# Microcontrolador.net
KiCad netlist of a schematic drawn in Altium Designer
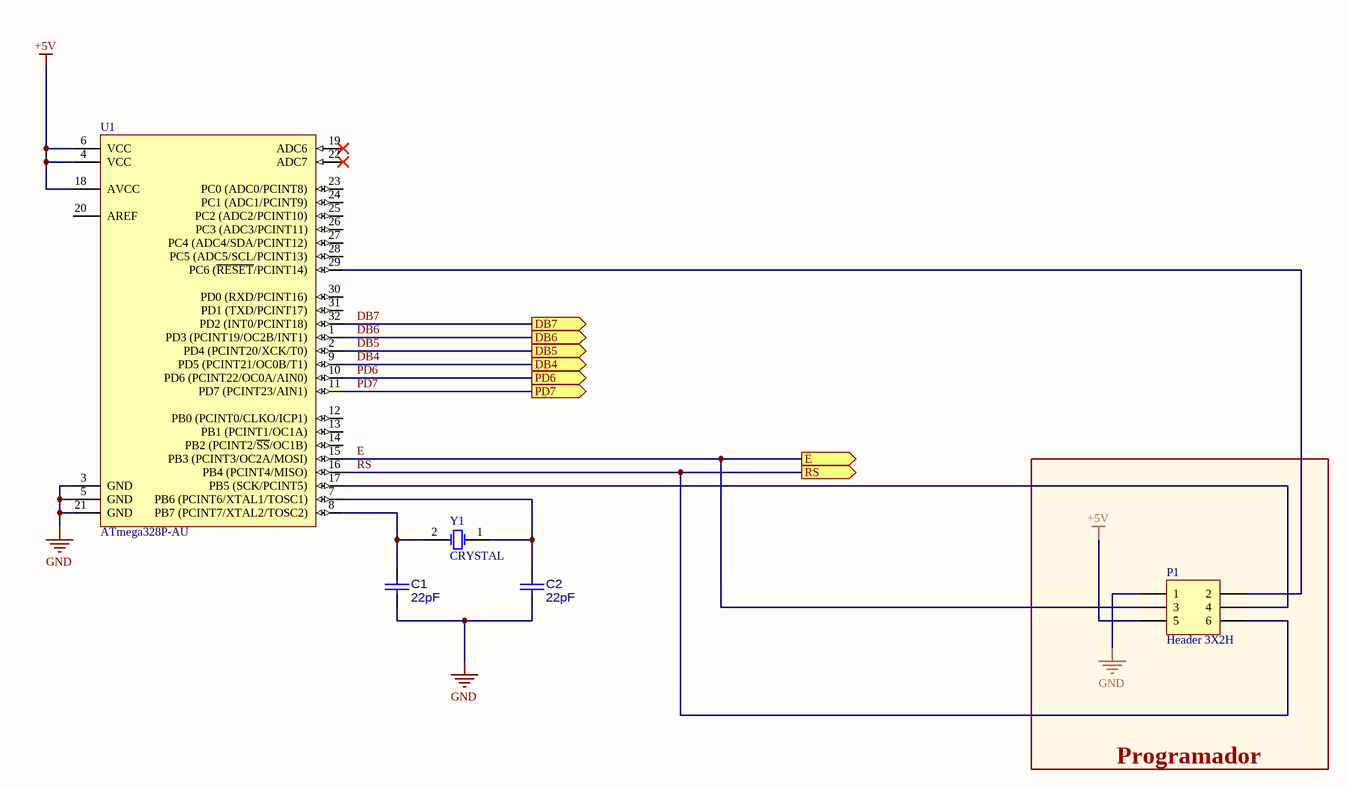
[diagram p0: Microcontrolador.SchDoc]

(export (version "E")
  (design (tool "Eeschema 10.0.6"))
  (components
    (comp (ref "C1")
      (value "22pF")
      (footprint "CAP0805")
      (libsource (lib "Desafio_Hardware_Firmware_Nathania") (part "CAP_4"))
    )
    (comp (ref "C2")
      (value "22pF")
      (footprint "CAP0805")
      (libsource (lib "Desafio_Hardware_Firmware_Nathania") (part "CAP_4"))
    )
    (comp (ref "P1")
      (value "Header 3X2H")
      (footprint "HDR-2X3")
      (description "Header, 3-Pin, Dual row, Right Angle")
      (fields (field (name "PUBLISHER") "Altium Limited"))
      (libsource (lib "Miscellaneous Connectors") (part "Header 3X2H"))
    )
    (comp (ref "U1")
      (value "ATmega328P-AU")
      (footprint "32A")
      (fields (field (name "PUBLISHER") "Altium Limited"))
      (libsource (lib "Desafio_Hardware_Firmware_Nathania") (part "ATmega328P-AU"))
    )
    (comp (ref "Y1")
      (value "CRYSTAL")
      (footprint "HC49S-SMD")
      (description "Crystal Oscillator")
      (libsource (lib "Desafio_Hardware_Firmware_Nathania") (part "CRYSTAL"))
    )
  )
  (nets
    (net (code "1") (name "+5V") (class "Default")
      (node (ref "P1") (pin "5") (pinfunction "5_5") (pintype "passive"))
      (node (ref "U1") (pin "18") (pinfunction "AVCC_18") (pintype "power_in"))
      (node (ref "U1") (pin "4") (pinfunction "VCC_4") (pintype "power_in"))
      (node (ref "U1") (pin "6") (pinfunction "VCC_6") (pintype "power_in"))
    )
    (net (code "2") (name "/DB4") (class "Default")
      (node (ref "U1") (pin "9") (pinfunction "PD5_(PCINT21/OC0B/T1)_9") (pintype "bidirectional"))
    )
    (net (code "3") (name "/DB5") (class "Default")
      (node (ref "U1") (pin "2") (pinfunction "PD4_(PCINT20/XCK/T0)_2") (pintype "bidirectional"))
    )
    (net (code "4") (name "/DB6") (class "Default")
      (node (ref "U1") (pin "1") (pinfunction "PD3_(PCINT19/OC2B/INT1)_1") (pintype "bidirectional"))
    )
    (net (code "5") (name "/DB7") (class "Default")
      (node (ref "U1") (pin "32") (pinfunction "PD2_(INT0/PCINT18)_32") (pintype "bidirectional"))
    )
    (net (code "6") (name "/E") (class "Default")
      (node (ref "P1") (pin "3") (pinfunction "3_3") (pintype "passive"))
      (node (ref "U1") (pin "15") (pinfunction "PB3_(PCINT3/OC2A/MOSI)_15") (pintype "bidirectional"))
    )
    (net (code "7") (name "/PD6") (class "Default")
      (node (ref "U1") (pin "10") (pinfunction "PD6_(PCINT22/OC0A/AIN0)_10") (pintype "bidirectional"))
    )
    (net (code "8") (name "/PD7") (class "Default")
      (node (ref "U1") (pin "11") (pinfunction "PD7_(PCINT23/AIN1)_11") (pintype "bidirectional"))
    )
    (net (code "9") (name "/RS") (class "Default")
      (node (ref "P1") (pin "6") (pinfunction "6_6") (pintype "passive"))
      (node (ref "U1") (pin "16") (pinfunction "PB4_(PCINT4/MISO)_16") (pintype "bidirectional"))
    )
    (net (code "10") (name "GND") (class "Default")
      (node (ref "C1") (pin "2") (pintype "passive"))
      (node (ref "C2") (pin "2") (pintype "passive"))
      (node (ref "P1") (pin "1") (pinfunction "1_1") (pintype "passive"))
      (node (ref "U1") (pin "21") (pinfunction "GND_21") (pintype "power_in"))
      (node (ref "U1") (pin "3") (pinfunction "GND_3") (pintype "power_in"))
      (node (ref "U1") (pin "5") (pinfunction "GND_5") (pintype "power_in"))
    )
    (net (code "11") (name "Net-(U1-PB5_(SCK{slash}PCINT5))") (class "Default")
      (node (ref "P1") (pin "4") (pinfunction "4_4") (pintype "passive"))
      (node (ref "U1") (pin "17") (pinfunction "PB5_(SCK/PCINT5)_17") (pintype "bidirectional"))
    )
    (net (code "12") (name "Net-(U1-PB6_(PCINT6{slash}XTAL1{slash}TOSC1))") (class "Default")
      (node (ref "C2") (pin "1") (pintype "passive"))
      (node (ref "U1") (pin "7") (pinfunction "PB6_(PCINT6/XTAL1/TOSC1)_7") (pintype "bidirectional"))
      (node (ref "Y1") (pin "1") (pinfunction "OSC1_1") (pintype "passive"))
    )
    (net (code "13") (name "Net-(U1-PB7_(PCINT7{slash}XTAL2{slash}TOSC2))") (class "Default")
      (node (ref "C1") (pin "1") (pintype "passive"))
      (node (ref "U1") (pin "8") (pinfunction "PB7_(PCINT7/XTAL2/TOSC2)_8") (pintype "bidirectional"))
      (node (ref "Y1") (pin "2") (pinfunction "OSC2_2") (pintype "passive"))
    )
    (net (code "14") (name "Net-(U1-PC6_(~{RESET}{slash}PCINT14))") (class "Default")
      (node (ref "P1") (pin "2") (pinfunction "2_2") (pintype "passive"))
      (node (ref "U1") (pin "29") (pinfunction "PC6_(~{RESET}/PCINT14)_29") (pintype "bidirectional"))
    )
    (net (code "15") (name "unconnected-(U1-ADC6-Pad19)") (class "Default")
      (node (ref "U1") (pin "19") (pinfunction "ADC6_19") (pintype "input+no_connect"))
    )
    (net (code "16") (name "unconnected-(U1-ADC7-Pad22)") (class "Default")
      (node (ref "U1") (pin "22") (pinfunction "ADC7_22") (pintype "input+no_connect"))
    )
    (net (code "17") (name "unconnected-(U1-AREF-Pad20)") (class "Default")
      (node (ref "U1") (pin "20") (pinfunction "AREF_20") (pintype "passive"))
    )
    (net (code "18") (name "unconnected-(U1-PB0_(PCINT0{slash}CLKO{slash}ICP1)-Pad12)") (class "Default")
      (node (ref "U1") (pin "12") (pinfunction "PB0_(PCINT0/CLKO/ICP1)_12") (pintype "bidirectional"))
    )
    (net (code "19") (name "unconnected-(U1-PB1_(PCINT1{slash}OC1A)-Pad13)") (class "Default")
      (node (ref "U1") (pin "13") (pinfunction "PB1_(PCINT1/OC1A)_13") (pintype "bidirectional"))
    )
    (net (code "20") (name "unconnected-(U1-PB2_(PCINT2{slash}~{SS}{slash}OC1B)-Pad14)") (class "Default")
      (node (ref "U1") (pin "14") (pinfunction "PB2_(PCINT2/~{SS}/OC1B)_14") (pintype "bidirectional"))
    )
    (net (code "21") (name "unconnected-(U1-PC0_(ADC0{slash}PCINT8)-Pad23)") (class "Default")
      (node (ref "U1") (pin "23") (pinfunction "PC0_(ADC0/PCINT8)_23") (pintype "bidirectional"))
    )
    (net (code "22") (name "unconnected-(U1-PC1_(ADC1{slash}PCINT9)-Pad24)") (class "Default")
      (node (ref "U1") (pin "24") (pinfunction "PC1_(ADC1/PCINT9)_24") (pintype "bidirectional"))
    )
    (net (code "23") (name "unconnected-(U1-PC2_(ADC2{slash}PCINT10)-Pad25)") (class "Default")
      (node (ref "U1") (pin "25") (pinfunction "PC2_(ADC2/PCINT10)_25") (pintype "bidirectional"))
    )
    (net (code "24") (name "unconnected-(U1-PC3_(ADC3{slash}PCINT11)-Pad26)") (class "Default")
      (node (ref "U1") (pin "26") (pinfunction "PC3_(ADC3/PCINT11)_26") (pintype "bidirectional"))
    )
    (net (code "25") (name "unconnected-(U1-PC4_(ADC4{slash}SDA{slash}PCINT12)-Pad27)") (class "Default")
      (node (ref "U1") (pin "27") (pinfunction "PC4_(ADC4/SDA/PCINT12)_27") (pintype "bidirectional"))
    )
    (net (code "26") (name "unconnected-(U1-PC5_(ADC5{slash}SCL{slash}PCINT13)-Pad28)") (class "Default")
      (node (ref "U1") (pin "28") (pinfunction "PC5_(ADC5/SCL/PCINT13)_28") (pintype "bidirectional"))
    )
    (net (code "27") (name "unconnected-(U1-PD0_(RXD{slash}PCINT16)-Pad30)") (class "Default")
      (node (ref "U1") (pin "30") (pinfunction "PD0_(RXD/PCINT16)_30") (pintype "bidirectional"))
    )
    (net (code "28") (name "unconnected-(U1-PD1_(TXD{slash}PCINT17)-Pad31)") (class "Default")
      (node (ref "U1") (pin "31") (pinfunction "PD1_(TXD/PCINT17)_31") (pintype "bidirectional"))
    )
  )
)
